# GPS.net
KiCad netlist of a schematic drawn in Altium Designer
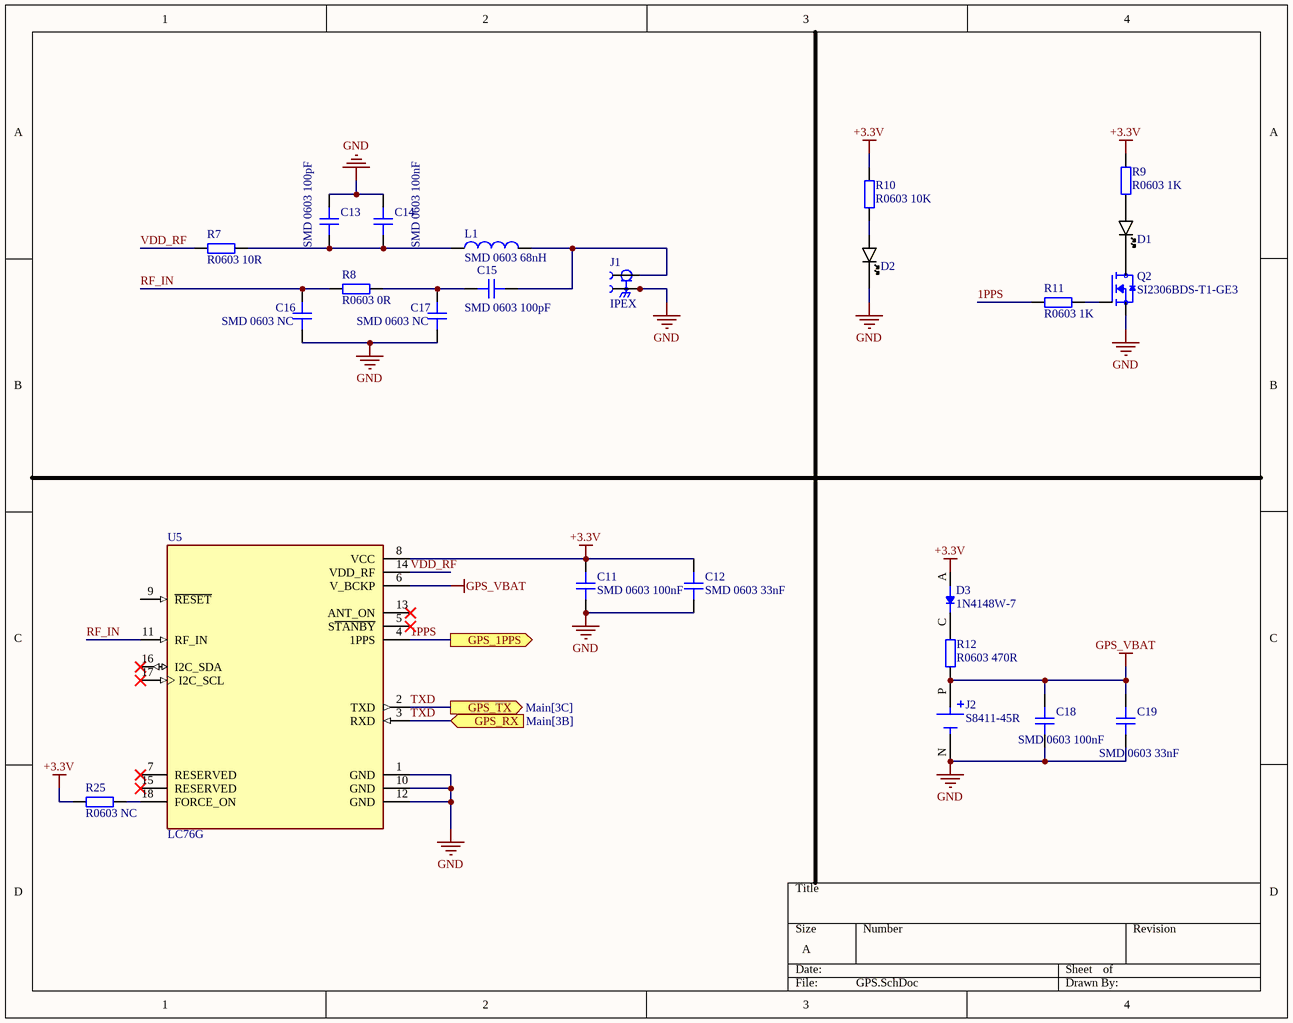
[diagram p0: GPS.SchDoc]

(export (version "E")
  (design (tool "Eeschema 10.0.6"))
  (components
    (comp (ref "C11")
      (value "SMD 0603 100nF")
      (footprint "CAP_0603")
      (description "Capacitor SMD 0603")
      (libsource (lib "Project") (part "CAP_0603"))
    )
    (comp (ref "C12")
      (value "SMD 0603 33nF")
      (footprint "CAP_0603")
      (description "Capacitor SMD 0603")
      (libsource (lib "Project") (part "CAP_0603"))
    )
    (comp (ref "C13")
      (value "SMD 0603 100pF")
      (footprint "CAP_0603")
      (description "Capacitor SMD 0603")
      (libsource (lib "Project") (part "CAP_0603"))
    )
    (comp (ref "C14")
      (value "SMD 0603 100nF")
      (footprint "CAP_0603")
      (description "Capacitor SMD 0603")
      (libsource (lib "Project") (part "CAP_0603"))
    )
    (comp (ref "C15")
      (value "SMD 0603 100pF")
      (footprint "CAP_0603")
      (description "Capacitor SMD 0603")
      (libsource (lib "Project") (part "CAP_0603"))
    )
    (comp (ref "C16")
      (value "SMD 0603 NC")
      (footprint "NC_0603")
      (description "Capacitor SMD 0603")
      (libsource (lib "Project") (part "CAP_0603"))
    )
    (comp (ref "C17")
      (value "SMD 0603 NC")
      (footprint "NC_0603")
      (description "Capacitor SMD 0603")
      (libsource (lib "Project") (part "CAP_0603"))
    )
    (comp (ref "C18")
      (value "SMD 0603 100nF")
      (footprint "CAP_0603")
      (description "Capacitor SMD 0603")
      (libsource (lib "Project") (part "CAP_0603"))
    )
    (comp (ref "C19")
      (value "SMD 0603 33nF")
      (footprint "CAP_0603")
      (description "Capacitor SMD 0603")
      (libsource (lib "Project") (part "CAP_0603"))
    )
    (comp (ref "D1")
      (value "BLUE")
      (footprint "LED_0805")
      (description "LED 0805 BLUE SMD")
      (libsource (lib "Project") (part "LED_0805"))
    )
    (comp (ref "D2")
      (value "~")
      (footprint "LED_0805")
      (description "LED 0805 BLUE SMD")
      (libsource (lib "Project") (part "LED_0805"))
    )
    (comp (ref "D3")
      (value "1N4148W-7")
      (footprint "SOD3715X135N")
      (description "Diode Standard 100 V 300mA (DC) Surface Mount SOD-123")
      (fields (field (name "MF") "Diodes Inc."))
      (libsource (lib "Project") (part "1N4148W-7"))
    )
    (comp (ref "J1")
      (value "IPEX")
      (footprint "IPEX_20279-001E-03")
      (fields (field (name "MF") "I-PEX") (field (name "MP") "20279-001E-03"))
      (libsource (lib "Project") (part "IPEX"))
    )
    (comp (ref "J2")
      (value "S8411-45R")
      (footprint "HARWIN_S8411-45R")
      (description "Coin Cell Battery Retainer, Horizontal SMT, for CR1220 Coin Cell Batteries, Tape & Reeled")
      (fields (field (name "MF") "Harwin"))
      (libsource (lib "Project") (part "S8411-45R"))
    )
    (comp (ref "L1")
      (value "SMD 0603 68nH")
      (footprint "0603 INDUCTOR")
      (description "Inductor with 0603 (1608)")
      (fields (field (name "MP") "LQW18AS22NG0CD") (field (name "MF") "Murata"))
      (libsource (lib "Project") (part "INDUCTOR_0603"))
    )
    (comp (ref "Q2")
      (value "SI2306BDS-T1-GE3")
      (footprint "SOT95P237X112-3N")
      (description "N-Channel 30 V 3.16A (Ta) 750mW (Ta) Surface Mount SOT-23-3 (TO-236)")
      (fields (field (name "MF") "Vishay Siliconix"))
      (libsource (lib "Project") (part "SI2306BDS-T1-GE3"))
    )
    (comp (ref "R7")
      (value "R0603 10R")
      (footprint "RES_0603")
      (description "Resistor SMD 0603")
      (libsource (lib "Project") (part "RES_0603"))
    )
    (comp (ref "R8")
      (value "R0603 0R")
      (footprint "RES_0603")
      (description "Resistor SMD 0603")
      (libsource (lib "Project") (part "RES_0603"))
    )
    (comp (ref "R9")
      (value "R0603 1K")
      (footprint "RES_0603")
      (description "Resistor SMD 0603")
      (libsource (lib "Project") (part "RES_0603"))
    )
    (comp (ref "R10")
      (value "R0603 10K")
      (footprint "RES_0603")
      (description "Resistor SMD 0603")
      (libsource (lib "Project") (part "RES_0603"))
    )
    (comp (ref "R11")
      (value "R0603 1K")
      (footprint "RES_0603")
      (description "Resistor SMD 0603")
      (libsource (lib "Project") (part "RES_0603"))
    )
    (comp (ref "R12")
      (value "R0603 470R")
      (footprint "RES_0603")
      (description "Resistor SMD 0603")
      (libsource (lib "Project") (part "RES_0603"))
    )
    (comp (ref "R25")
      (value "R0603 NC")
      (footprint "NC_0603")
      (description "Resistor SMD 0603")
      (libsource (lib "Project") (part "RES_0603"))
    )
    (comp (ref "U5")
      (value "LC76G")
      (footprint "XCVR_LC76G")
      (fields (field (name "MF") "Quectel"))
      (libsource (lib "Project") (part "LC76G"))
    )
  )
  (nets
    (net (code "1") (name "+3.3V") (class "Default")
      (node (ref "C11") (pin "2") (pinfunction "2_2") (pintype "passive"))
      (node (ref "C12") (pin "2") (pinfunction "2_2") (pintype "passive"))
      (node (ref "D3") (pin "A") (pinfunction "A_A") (pintype "passive"))
      (node (ref "R10") (pin "2") (pinfunction "2_2") (pintype "passive"))
      (node (ref "R25") (pin "1") (pinfunction "1_1") (pintype "passive"))
      (node (ref "R9") (pin "2") (pinfunction "2_2") (pintype "passive"))
      (node (ref "U5") (pin "8") (pinfunction "VCC_8") (pintype "power_in"))
    )
    (net (code "2") (name "/1PPS") (class "Default")
      (node (ref "R11") (pin "2") (pinfunction "2_2") (pintype "passive"))
      (node (ref "U5") (pin "4") (pinfunction "1PPS_4") (pintype "passive"))
    )
    (net (code "3") (name "/RF_IN") (class "Default")
      (node (ref "C16") (pin "1") (pinfunction "1_1") (pintype "passive"))
      (node (ref "R8") (pin "1") (pinfunction "1_1") (pintype "passive"))
      (node (ref "U5") (pin "11") (pinfunction "RF_IN_11") (pintype "input"))
    )
    (net (code "4") (name "/TXD") (class "Default")
      (node (ref "U5") (pin "2") (pinfunction "TXD_2") (pintype "output"))
      (node (ref "U5") (pin "3") (pinfunction "RXD_3") (pintype "input"))
    )
    (net (code "5") (name "/VDD_RF") (class "Default")
      (node (ref "R7") (pin "1") (pinfunction "1_1") (pintype "passive"))
      (node (ref "U5") (pin "14") (pinfunction "VDD_RF_14") (pintype "power_in"))
    )
    (net (code "6") (name "GND") (class "Default")
      (node (ref "C11") (pin "1") (pinfunction "1_1") (pintype "passive"))
      (node (ref "C12") (pin "1") (pinfunction "1_1") (pintype "passive"))
      (node (ref "C13") (pin "2") (pinfunction "2_2") (pintype "passive"))
      (node (ref "C14") (pin "2") (pinfunction "2_2") (pintype "passive"))
      (node (ref "C16") (pin "2") (pinfunction "2_2") (pintype "passive"))
      (node (ref "C17") (pin "2") (pinfunction "2_2") (pintype "passive"))
      (node (ref "C18") (pin "1") (pinfunction "1_1") (pintype "passive"))
      (node (ref "C19") (pin "1") (pinfunction "1_1") (pintype "passive"))
      (node (ref "D2") (pin "K") (pinfunction "K_K") (pintype "passive"))
      (node (ref "J1") (pin "2") (pinfunction "GROUND_2") (pintype "passive"))
      (node (ref "J1") (pin "3") (pinfunction "GROUND_3") (pintype "passive"))
      (node (ref "J2") (pin "N") (pinfunction "NEG_N") (pintype "passive"))
      (node (ref "Q2") (pin "2") (pinfunction "S_2") (pintype "passive"))
      (node (ref "U5") (pin "1") (pinfunction "GND_1") (pintype "power_in"))
      (node (ref "U5") (pin "10") (pinfunction "GND_10") (pintype "power_in"))
      (node (ref "U5") (pin "12") (pinfunction "GND_12") (pintype "power_in"))
    )
    (net (code "7") (name "GPS_VBAT") (class "Default")
      (node (ref "C18") (pin "2") (pinfunction "2_2") (pintype "passive"))
      (node (ref "C19") (pin "2") (pinfunction "2_2") (pintype "passive"))
      (node (ref "J2") (pin "P") (pinfunction "POS_P") (pintype "passive"))
      (node (ref "R12") (pin "1") (pinfunction "1_1") (pintype "passive"))
      (node (ref "U5") (pin "6") (pinfunction "V_BCKP_6") (pintype "power_in"))
    )
    (net (code "8") (name "Net-(C13-Pad1)") (class "Default")
      (node (ref "C13") (pin "1") (pinfunction "1_1") (pintype "passive"))
      (node (ref "C14") (pin "1") (pinfunction "1_1") (pintype "passive"))
      (node (ref "L1") (pin "1") (pinfunction "1_1") (pintype "passive"))
      (node (ref "R7") (pin "2") (pinfunction "2_2") (pintype "passive"))
    )
    (net (code "9") (name "Net-(C15-Pad1)") (class "Default")
      (node (ref "C15") (pin "1") (pinfunction "1_1") (pintype "passive"))
      (node (ref "C17") (pin "1") (pinfunction "1_1") (pintype "passive"))
      (node (ref "R8") (pin "2") (pinfunction "2_2") (pintype "passive"))
    )
    (net (code "10") (name "Net-(D1-PadA)") (class "Default")
      (node (ref "D1") (pin "A") (pinfunction "A_A") (pintype "passive"))
      (node (ref "R9") (pin "1") (pinfunction "1_1") (pintype "passive"))
    )
    (net (code "11") (name "Net-(D2-PadA)") (class "Default")
      (node (ref "D2") (pin "A") (pinfunction "A_A") (pintype "passive"))
      (node (ref "R10") (pin "1") (pinfunction "1_1") (pintype "passive"))
    )
    (net (code "12") (name "Net-(D3-K)") (class "Default")
      (node (ref "D3") (pin "C") (pinfunction "K_C") (pintype "passive"))
      (node (ref "R12") (pin "2") (pinfunction "2_2") (pintype "passive"))
    )
    (net (code "13") (name "Net-(J1-SIGNAL)") (class "Default")
      (node (ref "C15") (pin "2") (pinfunction "2_2") (pintype "passive"))
      (node (ref "J1") (pin "1") (pinfunction "SIGNAL_1") (pintype "passive"))
      (node (ref "L1") (pin "2") (pinfunction "2_2") (pintype "passive"))
    )
    (net (code "14") (name "Net-(Q2-D)") (class "Default")
      (node (ref "D1") (pin "K") (pinfunction "K_K") (pintype "passive"))
      (node (ref "Q2") (pin "3") (pinfunction "D_3") (pintype "passive"))
    )
    (net (code "15") (name "Net-(Q2-G)") (class "Default")
      (node (ref "Q2") (pin "1") (pinfunction "G_1") (pintype "passive"))
      (node (ref "R11") (pin "1") (pinfunction "1_1") (pintype "passive"))
    )
    (net (code "16") (name "Net-(U5-FORCE_ON)") (class "Default")
      (node (ref "R25") (pin "2") (pinfunction "2_2") (pintype "passive"))
      (node (ref "U5") (pin "18") (pinfunction "FORCE_ON_18") (pintype "passive"))
    )
    (net (code "17") (name "unconnected-(U5-ANT_ON-Pad13)") (class "Default")
      (node (ref "U5") (pin "13") (pinfunction "ANT_ON_13") (pintype "passive+no_connect"))
    )
    (net (code "18") (name "unconnected-(U5-I2C_SCL-Pad17)") (class "Default")
      (node (ref "U5") (pin "17") (pinfunction "I2C_SCL_17") (pintype "input+no_connect"))
    )
    (net (code "19") (name "unconnected-(U5-I2C_SDA-Pad16)") (class "Default")
      (node (ref "U5") (pin "16") (pinfunction "I2C_SDA_16") (pintype "bidirectional+no_connect"))
    )
    (net (code "20") (name "unconnected-(U5-RESERVED-Pad7)") (class "Default")
      (node (ref "U5") (pin "7") (pinfunction "RESERVED_7") (pintype "passive+no_connect"))
    )
    (net (code "21") (name "unconnected-(U5-RESERVED-Pad15)") (class "Default")
      (node (ref "U5") (pin "15") (pinfunction "RESERVED_15") (pintype "passive+no_connect"))
    )
    (net (code "22") (name "unconnected-(U5-S~{TANBY}-Pad5)") (class "Default")
      (node (ref "U5") (pin "5") (pinfunction "S~{TANBY}_5") (pintype "passive+no_connect"))
    )
    (net (code "23") (name "unconnected-(U5-~{RESET}-Pad9)") (class "Default")
      (node (ref "U5") (pin "9") (pinfunction "~{RESET}_9") (pintype "input"))
    )
  )
)
